# FUFO.net
KiCad netlist of a schematic drawn in Altium Designer
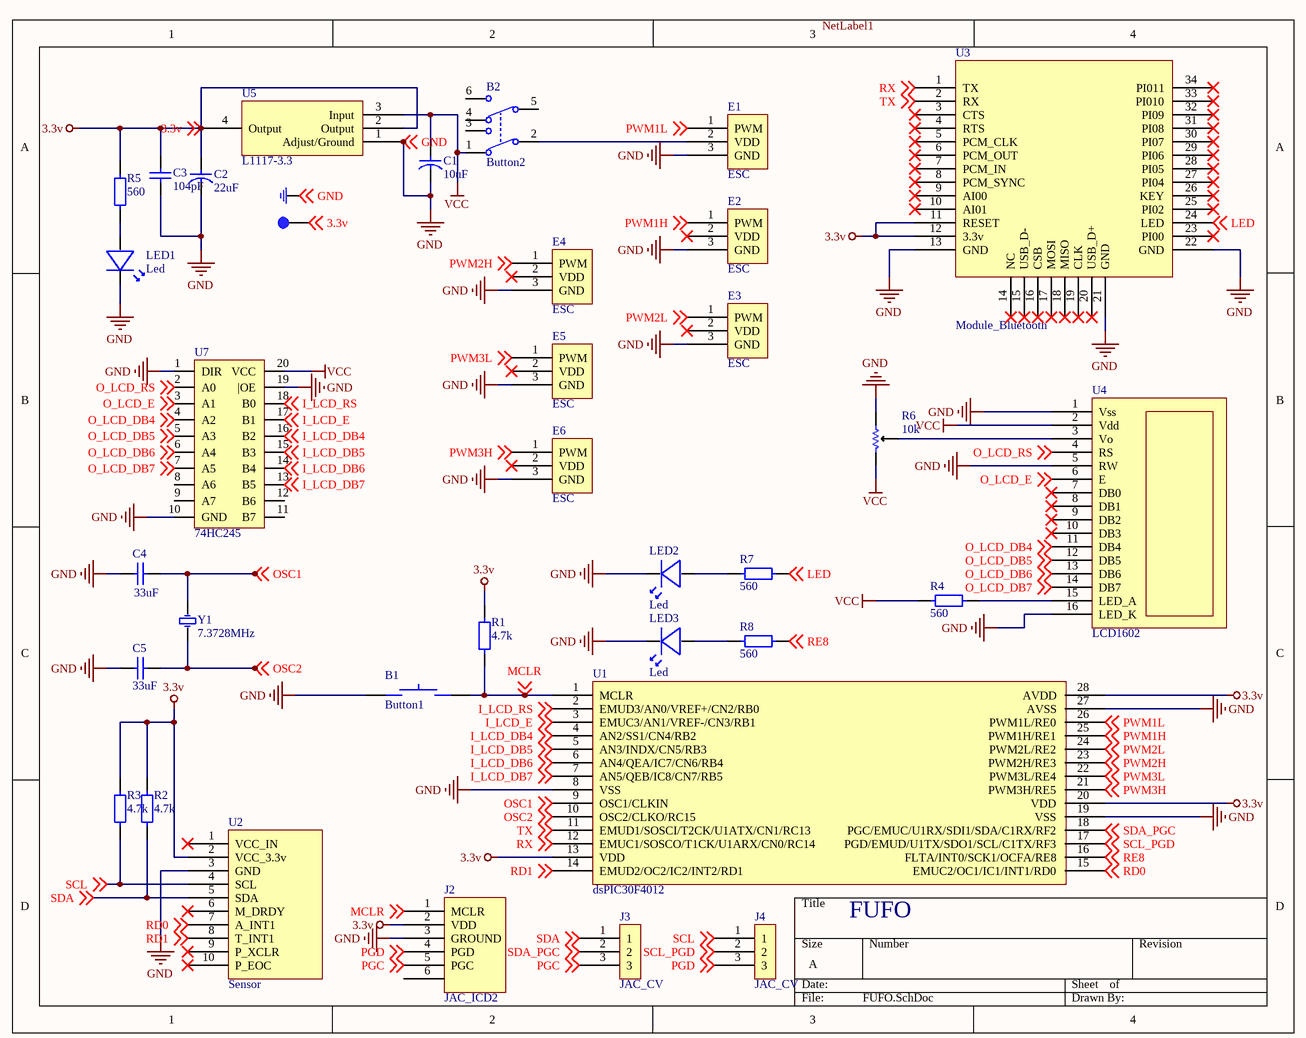
[diagram p0: FUFO.SchDoc]

(export (version "E")
  (design (tool "Eeschema 10.0.6"))
  (components
    (comp (ref "3.3v") (value "3.3v") (footprint "3.3v") (libsource (lib "FUFO") (part "3.3v")))
    (comp (ref "B1") (value "Button1") (footprint "Button1") (libsource (lib "FUFO") (part "Button1")))
    (comp (ref "B2") (value "Button2") (footprint "Button2") (libsource (lib "FUFO") (part "Button2")))
    (comp (ref "C1")
      (value "10uF")
      (footprint "Capacitor2")
      (description "Capacitor2")
      (libsource (lib "FUFO") (part "Capacitor2"))
    )
    (comp (ref "C2")
      (value "22uF")
      (footprint "Capacitor3")
      (description "Capacitor3")
      (libsource (lib "FUFO") (part "Capacitor3"))
    )
    (comp (ref "C3")
      (value "104pF")
      (footprint "Capacitor1")
      (description "Capacitor1")
      (libsource (lib "FUFO") (part "Capacitor1"))
    )
    (comp (ref "C4")
      (value "33uF")
      (footprint "Capacitor1")
      (description "Capacitor1")
      (libsource (lib "FUFO") (part "Capacitor1"))
    )
    (comp (ref "C5")
      (value "33uF")
      (footprint "Capacitor1")
      (description "Capacitor1")
      (libsource (lib "FUFO") (part "Capacitor1"))
    )
    (comp (ref "E1") (value "ESC") (footprint "ESC") (libsource (lib "FUFO") (part "ESC")))
    (comp (ref "E2") (value "ESC") (footprint "ESC") (libsource (lib "FUFO") (part "ESC")))
    (comp (ref "E3") (value "ESC") (footprint "ESC") (libsource (lib "FUFO") (part "ESC")))
    (comp (ref "E4") (value "ESC") (footprint "ESC") (libsource (lib "FUFO") (part "ESC")))
    (comp (ref "E5") (value "ESC") (footprint "ESC") (libsource (lib "FUFO") (part "ESC")))
    (comp (ref "E6") (value "ESC") (footprint "ESC") (libsource (lib "FUFO") (part "ESC")))
    (comp (ref "GND") (value "GND") (footprint "GND") (libsource (lib "FUFO") (part "GND")))
    (comp (ref "J2") (value "JAC_ICD2") (footprint "JAC_ICD2") (libsource (lib "FUFO") (part "JAC_ICD2")))
    (comp (ref "J3") (value "JAC_CV") (footprint "JAC_CV") (libsource (lib "FUFO") (part "JAC_CV")))
    (comp (ref "J4") (value "JAC_CV") (footprint "JAC_CV") (libsource (lib "FUFO") (part "JAC_CV")))
    (comp (ref "LED1") (value "Led") (footprint "LED") (libsource (lib "FUFO") (part "Led")))
    (comp (ref "LED2") (value "Led") (footprint "LED") (libsource (lib "FUFO") (part "Led")))
    (comp (ref "LED3") (value "Led") (footprint "LED") (libsource (lib "FUFO") (part "Led")))
    (comp (ref "R1") (value "4.7k") (footprint "Resistor") (libsource (lib "FUFO") (part "Resistor")))
    (comp (ref "R2") (value "4.7k") (footprint "Resistor") (libsource (lib "FUFO") (part "Resistor")))
    (comp (ref "R3") (value "4.7k") (footprint "Resistor") (libsource (lib "FUFO") (part "Resistor")))
    (comp (ref "R4") (value "560") (footprint "Resistor") (libsource (lib "FUFO") (part "Resistor")))
    (comp (ref "R5") (value "560") (footprint "Resistor") (libsource (lib "FUFO") (part "Resistor")))
    (comp (ref "R6") (value "10k") (footprint "BienTro") (libsource (lib "FUFO") (part "BienTro")))
    (comp (ref "R7") (value "560") (footprint "Resistor") (libsource (lib "FUFO") (part "Resistor")))
    (comp (ref "R8") (value "560") (footprint "Resistor") (libsource (lib "FUFO") (part "Resistor")))
    (comp (ref "U1")
      (value "dsPIC30F4012")
      (footprint "dsPIC30F4012")
      (libsource (lib "FUFO") (part "dsPIC30F4012"))
    )
    (comp (ref "U2") (value "Sensor") (footprint "Sensor") (libsource (lib "FUFO") (part "Sensor")))
    (comp (ref "U3")
      (value "Module_Bluetooth")
      (footprint "Module_Bluetooth")
      (libsource (lib "FUFO") (part "Module_Bluetooth"))
    )
    (comp (ref "U4") (value "LCD1602") (footprint "LCD1602") (libsource (lib "FUFO") (part "LCD1602")))
    (comp (ref "U5")
      (value "L1117-3.3")
      (footprint "L1117 - 3.3")
      (libsource (lib "FUFO") (part "L1117-3.3"))
    )
    (comp (ref "U7") (value "74HC245") (footprint "74HC245") (libsource (lib "FUFO") (part "74HC245")))
    (comp (ref "Y1") (value "7.3728MHz") (footprint "XTAL") (libsource (lib "FUFO") (part "XTAL")))
  )
  (nets
    (net (code "2") (name "3.3v") (class "Default")
      (node (ref "3.3v") (pin "0") (pinfunction "0_0") (pintype "passive"))
      (node (ref "C2") (pin "1") (pinfunction "1_1") (pintype "passive"))
      (node (ref "C3") (pin "2") (pinfunction "2_2") (pintype "passive"))
      (node (ref "J2") (pin "2") (pinfunction "VDD_2") (pintype "passive"))
      (node (ref "R1") (pin "2") (pinfunction "2_2") (pintype "passive"))
      (node (ref "R2") (pin "2") (pinfunction "2_2") (pintype "passive"))
      (node (ref "R3") (pin "2") (pinfunction "2_2") (pintype "passive"))
      (node (ref "R5") (pin "2") (pinfunction "2_2") (pintype "passive"))
      (node (ref "U1") (pin "13") (pinfunction "VDD_13") (pintype "passive"))
      (node (ref "U1") (pin "20") (pinfunction "VDD_20") (pintype "passive"))
      (node (ref "U1") (pin "28") (pinfunction "AVDD_28") (pintype "passive"))
      (node (ref "U2") (pin "2") (pinfunction "VCC_3.3v_2") (pintype "passive"))
      (node (ref "U3") (pin "11") (pinfunction "RESET_11") (pintype "passive"))
      (node (ref "U3") (pin "12") (pinfunction "3.3v_12") (pintype "passive"))
      (node (ref "U5") (pin "2") (pinfunction "Output_2") (pintype "passive"))
      (node (ref "U5") (pin "4") (pinfunction "Output_4") (pintype "passive"))
    )
    (net (code "3") (name "GND") (class "Default")
      (node (ref "B1") (pin "1") (pinfunction "1_1") (pintype "passive"))
      (node (ref "C1") (pin "2") (pinfunction "2_2") (pintype "passive"))
      (node (ref "C2") (pin "2") (pinfunction "2_2") (pintype "passive"))
      (node (ref "C3") (pin "1") (pinfunction "1_1") (pintype "passive"))
      (node (ref "C4") (pin "1") (pinfunction "1_1") (pintype "passive"))
      (node (ref "C5") (pin "1") (pinfunction "1_1") (pintype "passive"))
      (node (ref "E1") (pin "3") (pinfunction "GND_3") (pintype "passive"))
      (node (ref "E2") (pin "3") (pinfunction "GND_3") (pintype "passive"))
      (node (ref "E3") (pin "3") (pinfunction "GND_3") (pintype "passive"))
      (node (ref "E4") (pin "3") (pinfunction "GND_3") (pintype "passive"))
      (node (ref "E5") (pin "3") (pinfunction "GND_3") (pintype "passive"))
      (node (ref "E6") (pin "3") (pinfunction "GND_3") (pintype "passive"))
      (node (ref "GND") (pin "0") (pinfunction "0_0") (pintype "passive"))
      (node (ref "J2") (pin "3") (pinfunction "GROUND_3") (pintype "passive"))
      (node (ref "LED1") (pin "2") (pinfunction "2_2") (pintype "passive"))
      (node (ref "LED2") (pin "2") (pinfunction "2_2") (pintype "passive"))
      (node (ref "LED3") (pin "2") (pinfunction "2_2") (pintype "passive"))
      (node (ref "R6") (pin "0") (pinfunction "0_0") (pintype "passive"))
      (node (ref "U1") (pin "19") (pinfunction "VSS_19") (pintype "passive"))
      (node (ref "U1") (pin "27") (pinfunction "AVSS_27") (pintype "passive"))
      (node (ref "U1") (pin "8") (pinfunction "VSS_8") (pintype "passive"))
      (node (ref "U2") (pin "3") (pinfunction "GND_3") (pintype "passive"))
      (node (ref "U3") (pin "13") (pinfunction "GND_13") (pintype "passive"))
      (node (ref "U3") (pin "21") (pinfunction "GND_21") (pintype "passive"))
      (node (ref "U3") (pin "22") (pinfunction "GND_22") (pintype "passive"))
      (node (ref "U4") (pin "1") (pinfunction "Vss_1") (pintype "passive"))
      (node (ref "U4") (pin "16") (pinfunction "LED_K_16") (pintype "passive"))
      (node (ref "U4") (pin "5") (pinfunction "RW_5") (pintype "passive"))
      (node (ref "U5") (pin "1") (pinfunction "Adjust/Ground_1") (pintype "passive"))
      (node (ref "U7") (pin "1") (pinfunction "DIR_1") (pintype "passive"))
      (node (ref "U7") (pin "10") (pinfunction "GND_10") (pintype "passive"))
      (node (ref "U7") (pin "19") (pinfunction "OE_19") (pintype "passive"))
    )
    (net (code "4") (name "I_LCD_DB4") (class "Default")
      (node (ref "U1") (pin "4") (pinfunction "AN2/SS1/CN4/RB2_4") (pintype "passive"))
      (node (ref "U7") (pin "16") (pinfunction "B2_16") (pintype "passive"))
    )
    (net (code "5") (name "I_LCD_DB5") (class "Default")
      (node (ref "U1") (pin "5") (pinfunction "AN3/INDX/CN5/RB3_5") (pintype "passive"))
      (node (ref "U7") (pin "15") (pinfunction "B3_15") (pintype "passive"))
    )
    (net (code "6") (name "I_LCD_DB6") (class "Default")
      (node (ref "U1") (pin "6") (pinfunction "AN4/QEA/IC7/CN6/RB4_6") (pintype "passive"))
      (node (ref "U7") (pin "14") (pinfunction "B4_14") (pintype "passive"))
    )
    (net (code "7") (name "I_LCD_DB7") (class "Default")
      (node (ref "U1") (pin "7") (pinfunction "AN5/QEB/IC8/CN7/RB5_7") (pintype "passive"))
      (node (ref "U7") (pin "13") (pinfunction "B5_13") (pintype "passive"))
    )
    (net (code "8") (name "I_LCD_E") (class "Default")
      (node (ref "U1") (pin "3") (pinfunction "EMUC3/AN1/VREF-/CN3/RB1_3") (pintype "passive"))
      (node (ref "U7") (pin "17") (pinfunction "B1_17") (pintype "passive"))
    )
    (net (code "9") (name "I_LCD_RS") (class "Default")
      (node (ref "U1") (pin "2") (pinfunction "EMUD3/AN0/VREF+/CN2/RB0_2") (pintype "passive"))
      (node (ref "U7") (pin "18") (pinfunction "B0_18") (pintype "passive"))
    )
    (net (code "10") (name "LED") (class "Default")
      (node (ref "R7") (pin "2") (pinfunction "2_2") (pintype "passive"))
      (node (ref "U3") (pin "24") (pinfunction "LED_24") (pintype "passive"))
    )
    (net (code "11") (name "MCLR") (class "Default")
      (node (ref "B1") (pin "2") (pinfunction "2_2") (pintype "passive"))
      (node (ref "J2") (pin "1") (pinfunction "MCLR_1") (pintype "passive"))
      (node (ref "R1") (pin "1") (pinfunction "1_1") (pintype "passive"))
      (node (ref "U1") (pin "1") (pinfunction "MCLR_1") (pintype "passive"))
    )
    (net (code "12") (name "Net-(B2-1)") (class "Default")
      (node (ref "B2") (pin "2") (pinfunction "1_2") (pintype "passive"))
      (node (ref "E1") (pin "2") (pinfunction "VDD_2") (pintype "passive"))
    )
    (net (code "13") (name "Net-(LED1-Pad1)") (class "Default")
      (node (ref "LED1") (pin "1") (pinfunction "1_1") (pintype "passive"))
      (node (ref "R5") (pin "1") (pinfunction "1_1") (pintype "passive"))
    )
    (net (code "14") (name "Net-(LED2-Pad1)") (class "Default")
      (node (ref "LED2") (pin "1") (pinfunction "1_1") (pintype "passive"))
      (node (ref "R7") (pin "1") (pinfunction "1_1") (pintype "passive"))
    )
    (net (code "15") (name "Net-(LED3-Pad1)") (class "Default")
      (node (ref "LED3") (pin "1") (pinfunction "1_1") (pintype "passive"))
      (node (ref "R8") (pin "1") (pinfunction "1_1") (pintype "passive"))
    )
    (net (code "16") (name "Net-(U4-LED_A)") (class "Default")
      (node (ref "R4") (pin "2") (pinfunction "2_2") (pintype "passive"))
      (node (ref "U4") (pin "15") (pinfunction "LED_A_15") (pintype "passive"))
    )
    (net (code "17") (name "Net-(U4-Vo)") (class "Default")
      (node (ref "R6") (pin "1") (pinfunction "1_1") (pintype "passive"))
      (node (ref "U4") (pin "3") (pinfunction "Vo_3") (pintype "passive"))
    )
    (net (code "18") (name "OSC1") (class "Default")
      (node (ref "C4") (pin "2") (pinfunction "2_2") (pintype "passive"))
      (node (ref "U1") (pin "9") (pinfunction "OSC1/CLKIN_9") (pintype "passive"))
      (node (ref "Y1") (pin "2") (pinfunction "2_2") (pintype "passive"))
    )
    (net (code "19") (name "OSC2") (class "Default")
      (node (ref "C5") (pin "2") (pinfunction "2_2") (pintype "passive"))
      (node (ref "U1") (pin "10") (pinfunction "OSC2/CLKO/RC15_10") (pintype "passive"))
      (node (ref "Y1") (pin "1") (pinfunction "1_1") (pintype "passive"))
    )
    (net (code "20") (name "O_LCD_DB4") (class "Default")
      (node (ref "U4") (pin "11") (pinfunction "DB4_11") (pintype "passive"))
      (node (ref "U7") (pin "4") (pinfunction "A2_4") (pintype "passive"))
    )
    (net (code "21") (name "O_LCD_DB5") (class "Default")
      (node (ref "U4") (pin "12") (pinfunction "DB5_12") (pintype "passive"))
      (node (ref "U7") (pin "5") (pinfunction "A3_5") (pintype "passive"))
    )
    (net (code "22") (name "O_LCD_DB6") (class "Default")
      (node (ref "U4") (pin "13") (pinfunction "DB6_13") (pintype "passive"))
      (node (ref "U7") (pin "6") (pinfunction "A4_6") (pintype "passive"))
    )
    (net (code "23") (name "O_LCD_DB7") (class "Default")
      (node (ref "U4") (pin "14") (pinfunction "DB7_14") (pintype "passive"))
      (node (ref "U7") (pin "7") (pinfunction "A5_7") (pintype "passive"))
    )
    (net (code "24") (name "O_LCD_E") (class "Default")
      (node (ref "U4") (pin "6") (pinfunction "E_6") (pintype "passive"))
      (node (ref "U7") (pin "3") (pinfunction "A1_3") (pintype "passive"))
    )
    (net (code "25") (name "O_LCD_RS") (class "Default")
      (node (ref "U4") (pin "4") (pinfunction "RS_4") (pintype "passive"))
      (node (ref "U7") (pin "2") (pinfunction "A0_2") (pintype "passive"))
    )
    (net (code "26") (name "PGC") (class "Default")
      (node (ref "J2") (pin "5") (pinfunction "PGC_5") (pintype "passive"))
      (node (ref "J3") (pin "3") (pinfunction "3_3") (pintype "passive"))
    )
    (net (code "27") (name "PGD") (class "Default")
      (node (ref "J2") (pin "4") (pinfunction "PGD_4") (pintype "passive"))
      (node (ref "J4") (pin "3") (pinfunction "3_3") (pintype "passive"))
    )
    (net (code "28") (name "PWM1H") (class "Default")
      (node (ref "E2") (pin "1") (pinfunction "PWM_1") (pintype "passive"))
      (node (ref "U1") (pin "25") (pinfunction "PWM1H/RE1_25") (pintype "passive"))
    )
    (net (code "29") (name "PWM1L") (class "Default")
      (node (ref "E1") (pin "1") (pinfunction "PWM_1") (pintype "passive"))
      (node (ref "U1") (pin "26") (pinfunction "PWM1L/RE0_26") (pintype "passive"))
    )
    (net (code "30") (name "PWM2H") (class "Default")
      (node (ref "E4") (pin "1") (pinfunction "PWM_1") (pintype "passive"))
      (node (ref "U1") (pin "23") (pinfunction "PWM2H/RE3_23") (pintype "passive"))
    )
    (net (code "31") (name "PWM2L") (class "Default")
      (node (ref "E3") (pin "1") (pinfunction "PWM_1") (pintype "passive"))
      (node (ref "U1") (pin "24") (pinfunction "PWM2L/RE2_24") (pintype "passive"))
    )
    (net (code "32") (name "PWM3H") (class "Default")
      (node (ref "E6") (pin "1") (pinfunction "PWM_1") (pintype "passive"))
      (node (ref "U1") (pin "21") (pinfunction "PWM3H/RE5_21") (pintype "passive"))
    )
    (net (code "33") (name "PWM3L") (class "Default")
      (node (ref "E5") (pin "1") (pinfunction "PWM_1") (pintype "passive"))
      (node (ref "U1") (pin "22") (pinfunction "PWM3L/RE4_22") (pintype "passive"))
    )
    (net (code "34") (name "RD0") (class "Default")
      (node (ref "U1") (pin "15") (pinfunction "EMUC2/OC1/IC1/INT1/RD0_15") (pintype "passive"))
      (node (ref "U2") (pin "7") (pinfunction "A_INT1_7") (pintype "passive"))
    )
    (net (code "35") (name "RD1") (class "Default")
      (node (ref "U1") (pin "14") (pinfunction "EMUD2/OC2/IC2/INT2/RD1_14") (pintype "passive"))
      (node (ref "U2") (pin "8") (pinfunction "T_INT1_8") (pintype "passive"))
    )
    (net (code "36") (name "RE8") (class "Default")
      (node (ref "R8") (pin "2") (pinfunction "2_2") (pintype "passive"))
      (node (ref "U1") (pin "16") (pinfunction "FLTA/INT0/SCK1/OCFA/RE8_16") (pintype "passive"))
    )
    (net (code "37") (name "RX") (class "Default")
      (node (ref "U1") (pin "12") (pinfunction "EMUC1/SOSCO/T1CK/U1ARX/CN0/RC14_12") (pintype "passive"))
      (node (ref "U3") (pin "1") (pinfunction "TX_1") (pintype "passive"))
    )
    (net (code "38") (name "SCL") (class "Default")
      (node (ref "J4") (pin "1") (pinfunction "1_1") (pintype "passive"))
      (node (ref "R3") (pin "1") (pinfunction "1_1") (pintype "passive"))
      (node (ref "U2") (pin "4") (pinfunction "SCL_4") (pintype "passive"))
    )
    (net (code "39") (name "SCL_PGD") (class "Default")
      (node (ref "J4") (pin "2") (pinfunction "2_2") (pintype "passive"))
      (node (ref "U1") (pin "17") (pinfunction "PGD/EMUD/U1TX/SDO1/SCL/C1TX/RF3_17") (pintype "passive"))
    )
    (net (code "40") (name "SDA") (class "Default")
      (node (ref "J3") (pin "1") (pinfunction "1_1") (pintype "passive"))
      (node (ref "R2") (pin "1") (pinfunction "1_1") (pintype "passive"))
      (node (ref "U2") (pin "5") (pinfunction "SDA_5") (pintype "passive"))
    )
    (net (code "41") (name "SDA_PGC") (class "Default")
      (node (ref "J3") (pin "2") (pinfunction "2_2") (pintype "passive"))
      (node (ref "U1") (pin "18") (pinfunction "PGC/EMUC/U1RX/SDI1/SDA/C1RX/RF2_18") (pintype "passive"))
    )
    (net (code "42") (name "TX") (class "Default")
      (node (ref "U1") (pin "11") (pinfunction "EMUD1/SOSCI/T2CK/U1ATX/CN1/RC13_11") (pintype "passive"))
      (node (ref "U3") (pin "2") (pinfunction "RX_2") (pintype "passive"))
    )
    (net (code "43") (name "VCC") (class "Default")
      (node (ref "B2") (pin "1") (pinfunction "4_1") (pintype "passive"))
      (node (ref "C1") (pin "1") (pinfunction "1_1") (pintype "passive"))
      (node (ref "R4") (pin "1") (pinfunction "1_1") (pintype "passive"))
      (node (ref "R6") (pin "2") (pinfunction "2_2") (pintype "passive"))
      (node (ref "U4") (pin "2") (pinfunction "Vdd_2") (pintype "passive"))
      (node (ref "U5") (pin "3") (pinfunction "Input_3") (pintype "passive"))
      (node (ref "U7") (pin "20") (pinfunction "VCC_20") (pintype "passive"))
    )
    (net (code "44") (name "unconnected-(B2-5-Pad3)") (class "Default")
      (node (ref "B2") (pin "3") (pinfunction "5_3") (pintype "passive"))
    )
    (net (code "45") (name "unconnected-(B2-Pad4)") (class "Default")
      (node (ref "B2") (pin "4") (pinfunction "4_4") (pintype "passive"))
    )
    (net (code "46") (name "unconnected-(B2-Pad5)") (class "Default")
      (node (ref "B2") (pin "5") (pinfunction "5_5") (pintype "passive"))
    )
    (net (code "47") (name "unconnected-(B2-Pad6)") (class "Default")
      (node (ref "B2") (pin "6") (pinfunction "6_6") (pintype "passive"))
    )
    (net (code "48") (name "unconnected-(E2-VDD-Pad2)") (class "Default")
      (node (ref "E2") (pin "2") (pinfunction "VDD_2") (pintype "passive+no_connect"))
    )
    (net (code "49") (name "unconnected-(E3-VDD-Pad2)") (class "Default")
      (node (ref "E3") (pin "2") (pinfunction "VDD_2") (pintype "passive+no_connect"))
    )
    (net (code "50") (name "unconnected-(E4-VDD-Pad2)") (class "Default")
      (node (ref "E4") (pin "2") (pinfunction "VDD_2") (pintype "passive+no_connect"))
    )
    (net (code "51") (name "unconnected-(E5-VDD-Pad2)") (class "Default")
      (node (ref "E5") (pin "2") (pinfunction "VDD_2") (pintype "passive+no_connect"))
    )
    (net (code "52") (name "unconnected-(E6-VDD-Pad2)") (class "Default")
      (node (ref "E6") (pin "2") (pinfunction "VDD_2") (pintype "passive+no_connect"))
    )
    (net (code "53") (name "unconnected-(J2-Pad6)") (class "Default")
      (node (ref "J2") (pin "6") (pinfunction "6_6") (pintype "passive"))
    )
    (net (code "54") (name "unconnected-(U2-M_DRDY-Pad6)") (class "Default")
      (node (ref "U2") (pin "6") (pinfunction "M_DRDY_6") (pintype "passive+no_connect"))
    )
    (net (code "55") (name "unconnected-(U2-P_EOC-Pad10)") (class "Default")
      (node (ref "U2") (pin "10") (pinfunction "P_EOC_10") (pintype "passive+no_connect"))
    )
    (net (code "56") (name "unconnected-(U2-P_XCLR-Pad9)") (class "Default")
      (node (ref "U2") (pin "9") (pinfunction "P_XCLR_9") (pintype "passive+no_connect"))
    )
    (net (code "57") (name "unconnected-(U2-VCC_IN-Pad1)") (class "Default")
      (node (ref "U2") (pin "1") (pinfunction "VCC_IN_1") (pintype "passive+no_connect"))
    )
    (net (code "58") (name "unconnected-(U3-AI00-Pad9)") (class "Default")
      (node (ref "U3") (pin "9") (pinfunction "AI00_9") (pintype "passive+no_connect"))
    )
    (net (code "59") (name "unconnected-(U3-AI01-Pad10)") (class "Default")
      (node (ref "U3") (pin "10") (pinfunction "AI01_10") (pintype "passive+no_connect"))
    )
    (net (code "60") (name "unconnected-(U3-CLK-Pad19)") (class "Default")
      (node (ref "U3") (pin "19") (pinfunction "CLK_19") (pintype "passive+no_connect"))
    )
    (net (code "61") (name "unconnected-(U3-CSB-Pad16)") (class "Default")
      (node (ref "U3") (pin "16") (pinfunction "CSB_16") (pintype "passive+no_connect"))
    )
    (net (code "62") (name "unconnected-(U3-CTS-Pad3)") (class "Default")
      (node (ref "U3") (pin "3") (pinfunction "CTS_3") (pintype "passive+no_connect"))
    )
    (net (code "63") (name "unconnected-(U3-KEY-Pad26)") (class "Default")
      (node (ref "U3") (pin "26") (pinfunction "KEY_26") (pintype "passive+no_connect"))
    )
    (net (code "64") (name "unconnected-(U3-MISO-Pad18)") (class "Default")
      (node (ref "U3") (pin "18") (pinfunction "MISO_18") (pintype "passive+no_connect"))
    )
    (net (code "65") (name "unconnected-(U3-MOSI-Pad17)") (class "Default")
      (node (ref "U3") (pin "17") (pinfunction "MOSI_17") (pintype "passive+no_connect"))
    )
    (net (code "66") (name "unconnected-(U3-NC-Pad14)") (class "Default")
      (node (ref "U3") (pin "14") (pinfunction "NC_14") (pintype "passive+no_connect"))
    )
    (net (code "67") (name "unconnected-(U3-PCM_CLK-Pad5)") (class "Default")
      (node (ref "U3") (pin "5") (pinfunction "PCM_CLK_5") (pintype "passive+no_connect"))
    )
    (net (code "68") (name "unconnected-(U3-PCM_IN-Pad7)") (class "Default")
      (node (ref "U3") (pin "7") (pinfunction "PCM_IN_7") (pintype "passive+no_connect"))
    )
    (net (code "69") (name "unconnected-(U3-PCM_OUT-Pad6)") (class "Default")
      (node (ref "U3") (pin "6") (pinfunction "PCM_OUT_6") (pintype "passive+no_connect"))
    )
    (net (code "70") (name "unconnected-(U3-PCM_SYNC-Pad8)") (class "Default")
      (node (ref "U3") (pin "8") (pinfunction "PCM_SYNC_8") (pintype "passive+no_connect"))
    )
    (net (code "71") (name "unconnected-(U3-PI00-Pad23)") (class "Default")
      (node (ref "U3") (pin "23") (pinfunction "PI00_23") (pintype "passive+no_connect"))
    )
    (net (code "72") (name "unconnected-(U3-PI02-Pad25)") (class "Default")
      (node (ref "U3") (pin "25") (pinfunction "PI02_25") (pintype "passive+no_connect"))
    )
    (net (code "73") (name "unconnected-(U3-PI04-Pad27)") (class "Default")
      (node (ref "U3") (pin "27") (pinfunction "PI04_27") (pintype "passive+no_connect"))
    )
    (net (code "74") (name "unconnected-(U3-PI05-Pad28)") (class "Default")
      (node (ref "U3") (pin "28") (pinfunction "PI05_28") (pintype "passive+no_connect"))
    )
    (net (code "75") (name "unconnected-(U3-PI06-Pad29)") (class "Default")
      (node (ref "U3") (pin "29") (pinfunction "PI06_29") (pintype "passive+no_connect"))
    )
    (net (code "76") (name "unconnected-(U3-PI07-Pad30)") (class "Default")
      (node (ref "U3") (pin "30") (pinfunction "PI07_30") (pintype "passive+no_connect"))
    )
    (net (code "77") (name "unconnected-(U3-PI08-Pad31)") (class "Default")
      (node (ref "U3") (pin "31") (pinfunction "PI08_31") (pintype "passive+no_connect"))
    )
    (net (code "78") (name "unconnected-(U3-PI09-Pad32)") (class "Default")
      (node (ref "U3") (pin "32") (pinfunction "PI09_32") (pintype "passive+no_connect"))
    )
    (net (code "79") (name "unconnected-(U3-PI010-Pad33)") (class "Default")
      (node (ref "U3") (pin "33") (pinfunction "PI010_33") (pintype "passive+no_connect"))
    )
    (net (code "80") (name "unconnected-(U3-PI011-Pad34)") (class "Default")
      (node (ref "U3") (pin "34") (pinfunction "PI011_34") (pintype "passive+no_connect"))
    )
    (net (code "81") (name "unconnected-(U3-RTS-Pad4)") (class "Default")
      (node (ref "U3") (pin "4") (pinfunction "RTS_4") (pintype "passive+no_connect"))
    )
    (net (code "82") (name "unconnected-(U3-USB_D+-Pad20)") (class "Default")
      (node (ref "U3") (pin "20") (pinfunction "USB_D+_20") (pintype "passive+no_connect"))
    )
    (net (code "83") (name "unconnected-(U3-USB_D--Pad15)") (class "Default")
      (node (ref "U3") (pin "15") (pinfunction "USB_D-_15") (pintype "passive+no_connect"))
    )
    (net (code "84") (name "unconnected-(U4-DB0-Pad7)") (class "Default")
      (node (ref "U4") (pin "7") (pinfunction "DB0_7") (pintype "passive+no_connect"))
    )
    (net (code "85") (name "unconnected-(U4-DB1-Pad8)") (class "Default")
      (node (ref "U4") (pin "8") (pinfunction "DB1_8") (pintype "passive+no_connect"))
    )
    (net (code "86") (name "unconnected-(U4-DB2-Pad9)") (class "Default")
      (node (ref "U4") (pin "9") (pinfunction "DB2_9") (pintype "passive+no_connect"))
    )
    (net (code "87") (name "unconnected-(U4-DB3-Pad10)") (class "Default")
      (node (ref "U4") (pin "10") (pinfunction "DB3_10") (pintype "passive+no_connect"))
    )
    (net (code "88") (name "unconnected-(U7-A6-Pad8)") (class "Default")
      (node (ref "U7") (pin "8") (pinfunction "A6_8") (pintype "passive"))
    )
    (net (code "89") (name "unconnected-(U7-A7-Pad9)") (class "Default")
      (node (ref "U7") (pin "9") (pinfunction "A7_9") (pintype "passive"))
    )
    (net (code "90") (name "unconnected-(U7-B6-Pad12)") (class "Default")
      (node (ref "U7") (pin "12") (pinfunction "B6_12") (pintype "passive"))
    )
    (net (code "91") (name "unconnected-(U7-B7-Pad11)") (class "Default")
      (node (ref "U7") (pin "11") (pinfunction "B7_11") (pintype "passive"))
    )
  )
)
